# GMR.net
KiCad netlist of a schematic drawn in Altium Designer
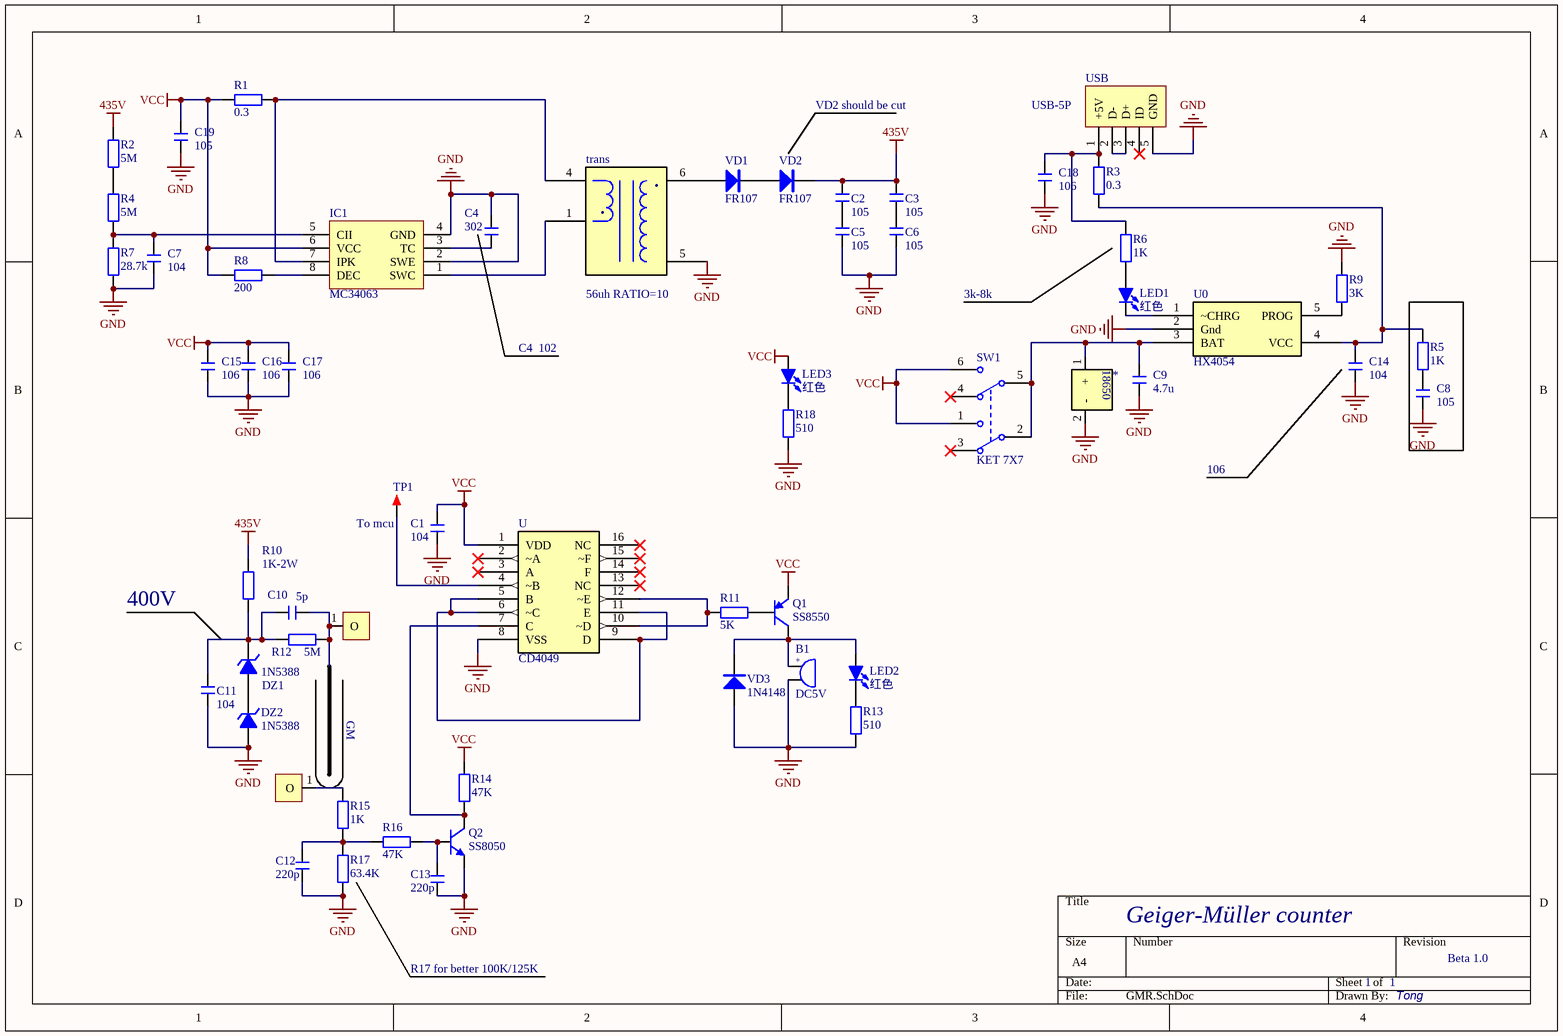
[diagram p0: GMR.SchDoc]

(export (version "E")
  (design (tool "Eeschema 10.0.6"))
  (components
    (comp (ref "*")
      (value "Component_1")
      (footprint "18650base")
      (libsource (lib "18650") (part "Component_1"))
    )
    (comp (ref "B1")
      (value "DC5V")
      (footprint "BEEP 7.6X12X7.5")
      (description "蜂鸣器")
      (fields (field (name "版权归属") "源创客"))
      (libsource (lib "未分类器件") (part "BEEP"))
    )
    (comp (ref "C1")
      (value "104")
      (footprint "C 0603")
      (description "瓷片电容-贴片")
      (libsource (lib "无源器件") (part "Cap-CER-SMD"))
    )
    (comp (ref "C2")
      (value "105")
      (footprint "C 1812")
      (description "瓷片电容-贴片")
      (libsource (lib "无源器件") (part "Cap-CER-SMD"))
    )
    (comp (ref "C3")
      (value "105")
      (footprint "C 1812")
      (description "瓷片电容-贴片")
      (libsource (lib "无源器件") (part "Cap-CER-SMD"))
    )
    (comp (ref "C4")
      (value "302")
      (footprint "C 0603")
      (description "瓷片电容-贴片")
      (libsource (lib "无源器件") (part "Cap-CER-SMD"))
    )
    (comp (ref "C5")
      (value "105")
      (footprint "C 1812")
      (description "瓷片电容-贴片")
      (libsource (lib "无源器件") (part "Cap-CER-SMD"))
    )
    (comp (ref "C6")
      (value "105")
      (footprint "C 1812")
      (description "瓷片电容-贴片")
      (libsource (lib "无源器件") (part "Cap-CER-SMD"))
    )
    (comp (ref "C7")
      (value "104")
      (footprint "C 0603")
      (description "瓷片电容-贴片")
      (libsource (lib "无源器件") (part "Cap-CER-SMD"))
    )
    (comp (ref "C8")
      (value "105")
      (footprint "C 0603")
      (description "瓷片电容-贴片")
      (libsource (lib "无源器件") (part "Cap-CER-SMD"))
    )
    (comp (ref "C9")
      (value "4.7u")
      (footprint "C 0603")
      (description "瓷片电容-贴片")
      (libsource (lib "无源器件") (part "Cap-CER-SMD"))
    )
    (comp (ref "C10")
      (value "5p")
      (footprint "C 1206")
      (description "瓷片电容-贴片")
      (libsource (lib "无源器件") (part "Cap-CER-SMD"))
    )
    (comp (ref "C11")
      (value "104")
      (footprint "C 1812")
      (description "瓷片电容-贴片")
      (libsource (lib "无源器件") (part "Cap-CER-SMD"))
    )
    (comp (ref "C12")
      (value "220p")
      (footprint "C 0603")
      (description "瓷片电容-贴片")
      (libsource (lib "无源器件") (part "Cap-CER-SMD"))
    )
    (comp (ref "C13")
      (value "220p")
      (footprint "C 0603")
      (description "瓷片电容-贴片")
      (libsource (lib "无源器件") (part "Cap-CER-SMD"))
    )
    (comp (ref "C14")
      (value "104")
      (footprint "C 0603")
      (description "瓷片电容-贴片")
      (libsource (lib "无源器件") (part "Cap-CER-SMD"))
    )
    (comp (ref "C15")
      (value "106")
      (footprint "C 0603")
      (description "瓷片电容-贴片")
      (libsource (lib "无源器件") (part "Cap-CER-SMD"))
    )
    (comp (ref "C16")
      (value "106")
      (footprint "C 0603")
      (description "瓷片电容-贴片")
      (libsource (lib "无源器件") (part "Cap-CER-SMD"))
    )
    (comp (ref "C17")
      (value "106")
      (footprint "C 0603")
      (description "瓷片电容-贴片")
      (libsource (lib "无源器件") (part "Cap-CER-SMD"))
    )
    (comp (ref "C18")
      (value "106")
      (footprint "C 0603")
      (description "瓷片电容-贴片")
      (libsource (lib "无源器件") (part "Cap-CER-SMD"))
    )
    (comp (ref "C19")
      (value "105")
      (footprint "C 0603")
      (description "瓷片电容-贴片")
      (libsource (lib "无源器件") (part "Cap-CER-SMD"))
    )
    (comp (ref "DZ1")
      (value "1N5388")
      (footprint "wydiode")
      (description "30V/0.5W稳压管")
      (fields (field (name "版权归属") "源创客"))
      (libsource (lib "二极管-整流桥") (part "1N5256"))
    )
    (comp (ref "DZ2")
      (value "1N5388")
      (footprint "wydiode")
      (description "30V/0.5W稳压管")
      (fields (field (name "版权归属") "源创客"))
      (libsource (lib "二极管-整流桥") (part "1N5256"))
    )
    (comp (ref "IC1")
      (value "MC34063")
      (footprint "SOP8_L")
      (description "DC升降压芯片")
      (fields (field (name "版权归属") "源创客"))
      (libsource (lib "IC芯片") (part "MC34063"))
    )
    (comp (ref "LED1")
      (value "红色")
      (footprint "LED 0603B")
      (description "贴片LED")
      (libsource (lib "声光-传感器") (part "LED-SMD"))
    )
    (comp (ref "LED2")
      (value "红色")
      (footprint "LED")
      (description "贴片LED")
      (libsource (lib "声光-传感器") (part "LED-SMD"))
    )
    (comp (ref "LED3")
      (value "红色")
      (footprint "LED")
      (description "贴片LED")
      (libsource (lib "声光-传感器") (part "LED-SMD"))
    )
    (comp (ref "Q1")
      (value "SS8550")
      (footprint "SOT23-3N")
      (description "高频放大-PNP型")
      (fields (field (name "版权归属") "源创客"))
      (libsource (lib "三极管") (part "8550-SMD"))
    )
    (comp (ref "Q2")
      (value "SS8050")
      (footprint "SOT23-3L")
      (description "高频放大-NPN型")
      (fields (field (name "版权归属") "源创客"))
      (libsource (lib "三极管") (part "8050-SMD"))
    )
    (comp (ref "R1")
      (value "0.3")
      (footprint "Res-SMD-1206")
      (description "固定电阻器-贴片")
      (libsource (lib "无源器件") (part "Res-Fixed-SMD"))
    )
    (comp (ref "R2")
      (value "5M")
      (footprint "Res-SMD-1206")
      (description "固定电阻器-贴片")
      (libsource (lib "无源器件") (part "Res-Fixed-SMD"))
    )
    (comp (ref "R3")
      (value "0.3")
      (footprint "Res-SMD-1206")
      (description "固定电阻器-贴片")
      (libsource (lib "无源器件") (part "Res-Fixed-SMD"))
    )
    (comp (ref "R4")
      (value "5M")
      (footprint "Res-SMD-1206")
      (description "固定电阻器-贴片")
      (libsource (lib "无源器件") (part "Res-Fixed-SMD"))
    )
    (comp (ref "R5")
      (value "1K")
      (footprint "Res-SMD-0603")
      (description "固定电阻器-贴片")
      (libsource (lib "无源器件") (part "Res-Fixed-SMD"))
    )
    (comp (ref "R6")
      (value "1K")
      (footprint "Res-SMD-0603")
      (description "固定电阻器-贴片")
      (libsource (lib "无源器件") (part "Res-Fixed-SMD"))
    )
    (comp (ref "R7")
      (value "28.7k")
      (footprint "Res-SMD-0603")
      (description "固定电阻器-贴片")
      (libsource (lib "无源器件") (part "Res-Fixed-SMD"))
    )
    (comp (ref "R8")
      (value "200")
      (footprint "Res-SMD-0603")
      (description "固定电阻器-贴片")
      (libsource (lib "无源器件") (part "Res-Fixed-SMD"))
    )
    (comp (ref "R9")
      (value "3K")
      (footprint "Res-SMD-0603")
      (description "固定电阻器-贴片")
      (libsource (lib "无源器件") (part "Res-Fixed-SMD"))
    )
    (comp (ref "R10")
      (value "1K-2W")
      (footprint "Res-Axial-2W")
      (description "固定电阻器-直插")
      (libsource (lib "无源器件") (part "Res-Fixed-Axial"))
    )
    (comp (ref "R11")
      (value "5K")
      (footprint "Res-SMD-0603")
      (description "固定电阻器-贴片")
      (libsource (lib "无源器件") (part "Res-Fixed-SMD"))
    )
    (comp (ref "R12")
      (value "5M")
      (footprint "Res-Axial-1/4W")
      (description "固定电阻器-直插")
      (libsource (lib "无源器件") (part "Res-Fixed-Axial"))
    )
    (comp (ref "R13")
      (value "510")
      (footprint "Res-SMD-0603")
      (description "固定电阻器-贴片")
      (libsource (lib "无源器件") (part "Res-Fixed-SMD"))
    )
    (comp (ref "R14")
      (value "47K")
      (footprint "Res-SMD-0603")
      (description "固定电阻器-贴片")
      (libsource (lib "无源器件") (part "Res-Fixed-SMD"))
    )
    (comp (ref "R15")
      (value "1K")
      (footprint "Res-SMD-0603")
      (description "固定电阻器-贴片")
      (libsource (lib "无源器件") (part "Res-Fixed-SMD"))
    )
    (comp (ref "R16")
      (value "47K")
      (footprint "Res-SMD-0603")
      (description "固定电阻器-贴片")
      (libsource (lib "无源器件") (part "Res-Fixed-SMD"))
    )
    (comp (ref "R17")
      (value "63.4K")
      (footprint "Res-SMD-0603")
      (description "固定电阻器-贴片")
      (libsource (lib "无源器件") (part "Res-Fixed-SMD"))
    )
    (comp (ref "R18")
      (value "510")
      (footprint "Res-SMD-0603")
      (description "固定电阻器-贴片")
      (libsource (lib "无源器件") (part "Res-Fixed-SMD"))
    )
    (comp (ref "SW1")
      (value "KET 7X7")
      (footprint "5.8*5.8")
      (description "7*7自锁开关")
      (fields (field (name "版权归属") "源创客"))
      (libsource (lib "按键-开关-继电器") (part "KET 7X7"))
    )
    (comp (ref "TP1")
      (value "To mcu")
      (footprint "TEST TP1.4_B")
      (description "测试环")
      (fields (field (name "版权归属") "源创客"))
      (libsource (lib "未分类器件") (part "TEST TP"))
    )
    (comp (ref "trans") (value "~") (footprint "trans") (libsource (lib "trans1") (part "Component_1")))
    (comp (ref "tube1")
      (value "tube1")
      (footprint "PCBComponent_1")
      (libsource (lib "") (part "Component_1_1"))
    )
    (comp (ref "tube2")
      (value "tube2")
      (footprint "PCBComponent_1")
      (libsource (lib "tubebase") (part "Component_1"))
    )
    (comp (ref "U") (value "CD4049") (footprint "SOP16_L") (libsource (lib "CD4049") (part "Component_1")))
    (comp (ref "U0") (value "HX4054") (footprint "SOT23-5L") (libsource (lib "HX4054A") (part "Component_1")))
    (comp (ref "USB")
      (value "USB-5P")
      (footprint "USB-MICRO_B")
      (description "微型USB母座")
      (fields (field (name "版权归属") "源创客"))
      (libsource (lib "接口类") (part "USB-5P"))
    )
    (comp (ref "VD1")
      (value "FR107")
      (footprint "SOD-123F")
      (description "快恢复整流二极管")
      (fields (field (name "版权归属") "源创客"))
      (libsource (lib "二极管-整流桥") (part "FR107"))
    )
    (comp (ref "VD2")
      (value "FR107")
      (footprint "SOD-123F")
      (description "快恢复整流二极管")
      (fields (field (name "版权归属") "源创客"))
      (libsource (lib "二极管-整流桥") (part "FR107"))
    )
    (comp (ref "VD3")
      (value "1N4148")
      (footprint "SOD-123F")
      (description "高速开关二极管")
      (fields (field (name "版权归属") "源创客"))
      (libsource (lib "二极管-整流桥") (part "1N4148"))
    )
  )
  (nets
    (net (code "1") (name "435V") (class "Default")
      (node (ref "C2") (pin "1") (pinfunction "1_1") (pintype "passive"))
      (node (ref "C3") (pin "1") (pinfunction "1_1") (pintype "passive"))
      (node (ref "R10") (pin "2") (pinfunction "2_2") (pintype "passive"))
      (node (ref "R2") (pin "2") (pinfunction "2_2") (pintype "passive"))
      (node (ref "VD2") (pin "2") (pinfunction "K_2") (pintype "passive"))
    )
    (net (code "2") (name "GND") (class "Default")
      (node (ref "*") (pin "2") (pinfunction "-_2") (pintype "passive"))
      (node (ref "B1") (pin "2") (pinfunction "2_2") (pintype "passive"))
      (node (ref "C1") (pin "2") (pinfunction "2_2") (pintype "passive"))
      (node (ref "C11") (pin "2") (pinfunction "2_2") (pintype "passive"))
      (node (ref "C12") (pin "2") (pinfunction "2_2") (pintype "passive"))
      (node (ref "C13") (pin "2") (pinfunction "2_2") (pintype "passive"))
      (node (ref "C14") (pin "2") (pinfunction "2_2") (pintype "passive"))
      (node (ref "C15") (pin "2") (pinfunction "2_2") (pintype "passive"))
      (node (ref "C16") (pin "2") (pinfunction "2_2") (pintype "passive"))
      (node (ref "C17") (pin "2") (pinfunction "2_2") (pintype "passive"))
      (node (ref "C18") (pin "2") (pinfunction "2_2") (pintype "passive"))
      (node (ref "C19") (pin "2") (pinfunction "2_2") (pintype "passive"))
      (node (ref "C4") (pin "1") (pinfunction "1_1") (pintype "passive"))
      (node (ref "C5") (pin "2") (pinfunction "2_2") (pintype "passive"))
      (node (ref "C6") (pin "2") (pinfunction "2_2") (pintype "passive"))
      (node (ref "C7") (pin "2") (pinfunction "2_2") (pintype "passive"))
      (node (ref "C8") (pin "2") (pinfunction "2_2") (pintype "passive"))
      (node (ref "C9") (pin "2") (pinfunction "2_2") (pintype "passive"))
      (node (ref "DZ2") (pin "1") (pinfunction "A_1") (pintype "passive"))
      (node (ref "IC1") (pin "2") (pinfunction "SWE_2") (pintype "passive"))
      (node (ref "IC1") (pin "4") (pinfunction "GND_4") (pintype "passive"))
      (node (ref "Q2") (pin "2") (pinfunction "E_2") (pintype "passive"))
      (node (ref "R13") (pin "1") (pinfunction "1_1") (pintype "passive"))
      (node (ref "R17") (pin "1") (pinfunction "1_1") (pintype "passive"))
      (node (ref "R18") (pin "1") (pinfunction "1_1") (pintype "passive"))
      (node (ref "R7") (pin "1") (pinfunction "1_1") (pintype "passive"))
      (node (ref "R9") (pin "1") (pinfunction "1_1") (pintype "passive"))
      (node (ref "U") (pin "8") (pinfunction "VSS_8") (pintype "passive"))
      (node (ref "U0") (pin "2") (pinfunction "Gnd_2") (pintype "passive"))
      (node (ref "USB") (pin "5") (pinfunction "GND_5") (pintype "passive"))
      (node (ref "VD3") (pin "1") (pinfunction "A_1") (pintype "passive"))
      (node (ref "trans") (pin "5") (pinfunction "5_5") (pintype "passive"))
    )
    (net (code "3") (name "Net-(*-+)") (class "Default")
      (node (ref "*") (pin "1") (pinfunction "+_1") (pintype "passive"))
      (node (ref "C9") (pin "1") (pinfunction "1_1") (pintype "passive"))
      (node (ref "SW1") (pin "2") (pinfunction "COM2_2") (pintype "passive"))
      (node (ref "SW1") (pin "5") (pinfunction "COM2_5") (pintype "passive"))
      (node (ref "U0") (pin "3") (pinfunction "BAT_3") (pintype "passive"))
    )
    (net (code "4") (name "Net-(C2-Pad2)") (class "Default")
      (node (ref "C2") (pin "2") (pinfunction "2_2") (pintype "passive"))
      (node (ref "C5") (pin "1") (pinfunction "1_1") (pintype "passive"))
    )
    (net (code "5") (name "Net-(C3-Pad2)") (class "Default")
      (node (ref "C3") (pin "2") (pinfunction "2_2") (pintype "passive"))
      (node (ref "C6") (pin "1") (pinfunction "1_1") (pintype "passive"))
    )
    (net (code "6") (name "Net-(C12-Pad1)") (class "Default")
      (node (ref "C12") (pin "1") (pinfunction "1_1") (pintype "passive"))
      (node (ref "R15") (pin "1") (pinfunction "1_1") (pintype "passive"))
      (node (ref "R16") (pin "2") (pinfunction "2_2") (pintype "passive"))
      (node (ref "R17") (pin "2") (pinfunction "2_2") (pintype "passive"))
    )
    (net (code "7") (name "Net-(DZ1-A)") (class "Default")
      (node (ref "DZ1") (pin "1") (pinfunction "A_1") (pintype "passive"))
      (node (ref "DZ2") (pin "2") (pinfunction "K_2") (pintype "passive"))
    )
    (net (code "8") (name "Net-(DZ1-K)") (class "Default")
      (node (ref "C10") (pin "2") (pinfunction "2_2") (pintype "passive"))
      (node (ref "C11") (pin "1") (pinfunction "1_1") (pintype "passive"))
      (node (ref "DZ1") (pin "2") (pinfunction "K_2") (pintype "passive"))
      (node (ref "R10") (pin "1") (pinfunction "1_1") (pintype "passive"))
      (node (ref "R12") (pin "1") (pinfunction "1_1") (pintype "passive"))
    )
    (net (code "9") (name "Net-(IC1-CII)") (class "Default")
      (node (ref "C7") (pin "1") (pinfunction "1_1") (pintype "passive"))
      (node (ref "IC1") (pin "5") (pinfunction "CII_5") (pintype "passive"))
      (node (ref "R4") (pin "1") (pinfunction "1_1") (pintype "passive"))
      (node (ref "R7") (pin "2") (pinfunction "2_2") (pintype "passive"))
    )
    (net (code "10") (name "Net-(IC1-DEC)") (class "Default")
      (node (ref "IC1") (pin "8") (pinfunction "DEC_8") (pintype "passive"))
      (node (ref "R8") (pin "1") (pinfunction "1_1") (pintype "passive"))
    )
    (net (code "11") (name "Net-(IC1-IPK)") (class "Default")
      (node (ref "IC1") (pin "7") (pinfunction "IPK_7") (pintype "passive"))
      (node (ref "R1") (pin "1") (pinfunction "1_1") (pintype "passive"))
      (node (ref "trans") (pin "4") (pinfunction "4_4") (pintype "passive"))
    )
    (net (code "12") (name "Net-(IC1-SWC)") (class "Default")
      (node (ref "IC1") (pin "1") (pinfunction "SWC_1") (pintype "passive"))
      (node (ref "trans") (pin "1") (pinfunction "1_1") (pintype "passive"))
    )
    (net (code "13") (name "Net-(IC1-TC)") (class "Default")
      (node (ref "C4") (pin "2") (pinfunction "2_2") (pintype "passive"))
      (node (ref "IC1") (pin "3") (pinfunction "TC_3") (pintype "passive"))
    )
    (net (code "14") (name "Net-(LED1-A)") (class "Default")
      (node (ref "LED1") (pin "1") (pinfunction "A_1") (pintype "passive"))
      (node (ref "R6") (pin "2") (pinfunction "2_2") (pintype "passive"))
    )
    (net (code "15") (name "Net-(LED1-K)") (class "Default")
      (node (ref "LED1") (pin "2") (pinfunction "K_2") (pintype "passive"))
      (node (ref "U0") (pin "1") (pinfunction "~CHRG_1") (pintype "passive"))
    )
    (net (code "16") (name "Net-(LED2-A)") (class "Default")
      (node (ref "B1") (pin "1") (pinfunction "1_1") (pintype "passive"))
      (node (ref "LED2") (pin "1") (pinfunction "A_1") (pintype "passive"))
      (node (ref "Q1") (pin "3") (pinfunction "C_3") (pintype "passive"))
      (node (ref "VD3") (pin "2") (pinfunction "K_2") (pintype "passive"))
    )
    (net (code "17") (name "Net-(LED2-K)") (class "Default")
      (node (ref "LED2") (pin "2") (pinfunction "K_2") (pintype "passive"))
      (node (ref "R13") (pin "2") (pinfunction "2_2") (pintype "passive"))
    )
    (net (code "18") (name "Net-(LED3-K)") (class "Default")
      (node (ref "LED3") (pin "2") (pinfunction "K_2") (pintype "passive"))
      (node (ref "R18") (pin "2") (pinfunction "2_2") (pintype "passive"))
    )
    (net (code "19") (name "Net-(Q1-B)") (class "Default")
      (node (ref "Q1") (pin "1") (pinfunction "B_1") (pintype "passive"))
      (node (ref "R11") (pin "2") (pinfunction "2_2") (pintype "passive"))
    )
    (net (code "20") (name "Net-(Q2-B)") (class "Default")
      (node (ref "C13") (pin "1") (pinfunction "1_1") (pintype "passive"))
      (node (ref "Q2") (pin "1") (pinfunction "B_1") (pintype "passive"))
      (node (ref "R16") (pin "1") (pinfunction "1_1") (pintype "passive"))
    )
    (net (code "21") (name "Net-(Q2-C)") (class "Default")
      (node (ref "Q2") (pin "3") (pinfunction "C_3") (pintype "passive"))
      (node (ref "R14") (pin "2") (pinfunction "2_2") (pintype "passive"))
      (node (ref "U") (pin "7") (pinfunction "C_7") (pintype "passive"))
    )
    (net (code "22") (name "Net-(R2-Pad1)") (class "Default")
      (node (ref "R2") (pin "1") (pinfunction "1_1") (pintype "passive"))
      (node (ref "R4") (pin "2") (pinfunction "2_2") (pintype "passive"))
    )
    (net (code "23") (name "Net-(U-B)") (class "Default")
      (node (ref "U") (pin "11") (pinfunction "E_11") (pintype "passive"))
      (node (ref "U") (pin "5") (pinfunction "B_5") (pintype "passive"))
      (node (ref "U") (pin "6") (pinfunction "~C_6") (pintype "output"))
      (node (ref "U") (pin "9") (pinfunction "D_9") (pintype "passive"))
    )
    (net (code "24") (name "Net-(U-~B)") (class "Default")
      (node (ref "TP1") (pin "1") (pinfunction "1_1") (pintype "passive"))
      (node (ref "U") (pin "4") (pinfunction "~B_4") (pintype "output"))
    )
    (net (code "25") (name "Net-(U-~D)") (class "Default")
      (node (ref "R11") (pin "1") (pinfunction "1_1") (pintype "passive"))
      (node (ref "U") (pin "10") (pinfunction "~D_10") (pintype "output"))
      (node (ref "U") (pin "12") (pinfunction "~E_12") (pintype "output"))
    )
    (net (code "26") (name "Net-(U0-PROG)") (class "Default")
      (node (ref "R9") (pin "2") (pinfunction "2_2") (pintype "passive"))
      (node (ref "U0") (pin "5") (pinfunction "PROG_5") (pintype "passive"))
    )
    (net (code "27") (name "Net-(U0-VCC)") (class "Default")
      (node (ref "C14") (pin "1") (pinfunction "1_1") (pintype "passive"))
      (node (ref "R3") (pin "2") (pinfunction "2_2") (pintype "passive"))
      (node (ref "R5") (pin "1") (pinfunction "1_1") (pintype "passive"))
      (node (ref "U0") (pin "4") (pinfunction "VCC_4") (pintype "passive"))
    )
    (net (code "28") (name "Net-(USB-+5V)") (class "Default")
      (node (ref "C18") (pin "1") (pinfunction "1_1") (pintype "passive"))
      (node (ref "R3") (pin "1") (pinfunction "1_1") (pintype "passive"))
      (node (ref "R6") (pin "1") (pinfunction "1_1") (pintype "passive"))
      (node (ref "USB") (pin "1") (pinfunction "+5V_1") (pintype "passive"))
    )
    (net (code "29") (name "Net-(USB-D+)") (class "Default")
      (node (ref "USB") (pin "2") (pinfunction "D-_2") (pintype "passive"))
      (node (ref "USB") (pin "3") (pinfunction "D+_3") (pintype "passive"))
    )
    (net (code "30") (name "Net-(VD1-A)") (class "Default")
      (node (ref "VD1") (pin "1") (pinfunction "A_1") (pintype "passive"))
      (node (ref "trans") (pin "6") (pinfunction "6_6") (pintype "passive"))
    )
    (net (code "31") (name "Net-(VD1-K)") (class "Default")
      (node (ref "VD1") (pin "2") (pinfunction "K_2") (pintype "passive"))
      (node (ref "VD2") (pin "1") (pinfunction "A_1") (pintype "passive"))
    )
    (net (code "32") (name "Net-(tube1-O)") (class "Default")
      (node (ref "R15") (pin "2") (pinfunction "2_2") (pintype "passive"))
      (node (ref "tube1") (pin "1") (pinfunction "O_1") (pintype "passive"))
    )
    (net (code "33") (name "Net-(tube2-O)") (class "Default")
      (node (ref "C10") (pin "1") (pinfunction "1_1") (pintype "passive"))
      (node (ref "R12") (pin "2") (pinfunction "2_2") (pintype "passive"))
      (node (ref "tube2") (pin "1") (pinfunction "O_1") (pintype "passive"))
    )
    (net (code "34") (name "VCC") (class "Default")
      (node (ref "C1") (pin "1") (pinfunction "1_1") (pintype "passive"))
      (node (ref "C15") (pin "1") (pinfunction "1_1") (pintype "passive"))
      (node (ref "C16") (pin "1") (pinfunction "1_1") (pintype "passive"))
      (node (ref "C17") (pin "1") (pinfunction "1_1") (pintype "passive"))
      (node (ref "C19") (pin "1") (pinfunction "1_1") (pintype "passive"))
      (node (ref "IC1") (pin "6") (pinfunction "VCC_6") (pintype "passive"))
      (node (ref "LED3") (pin "1") (pinfunction "A_1") (pintype "passive"))
      (node (ref "Q1") (pin "2") (pinfunction "E_2") (pintype "passive"))
      (node (ref "R1") (pin "2") (pinfunction "2_2") (pintype "passive"))
      (node (ref "R14") (pin "1") (pinfunction "1_1") (pintype "passive"))
      (node (ref "R8") (pin "2") (pinfunction "2_2") (pintype "passive"))
      (node (ref "SW1") (pin "1") (pinfunction "NC1_1") (pintype "passive"))
      (node (ref "SW1") (pin "6") (pinfunction "NC2_6") (pintype "passive"))
      (node (ref "U") (pin "1") (pinfunction "VDD_1") (pintype "passive"))
    )
    (net (code "35") (name "unconnected-(C8-Pad1)") (class "Default")
      (node (ref "C8") (pin "1") (pinfunction "1_1") (pintype "passive"))
    )
    (net (code "36") (name "unconnected-(R5-Pad2)") (class "Default")
      (node (ref "R5") (pin "2") (pinfunction "2_2") (pintype "passive"))
    )
    (net (code "37") (name "unconnected-(SW1-NO1-Pad3)") (class "Default")
      (node (ref "SW1") (pin "3") (pinfunction "NO1_3") (pintype "passive+no_connect"))
    )
    (net (code "38") (name "unconnected-(SW1-NO2-Pad4)") (class "Default")
      (node (ref "SW1") (pin "4") (pinfunction "NO2_4") (pintype "passive+no_connect"))
    )
    (net (code "39") (name "unconnected-(U-A-Pad3)") (class "Default")
      (node (ref "U") (pin "3") (pinfunction "A_3") (pintype "passive+no_connect"))
    )
    (net (code "40") (name "unconnected-(U-F-Pad14)") (class "Default")
      (node (ref "U") (pin "14") (pinfunction "F_14") (pintype "passive+no_connect"))
    )
    (net (code "41") (name "unconnected-(U-NC-Pad13)") (class "Default")
      (node (ref "U") (pin "13") (pinfunction "NC_13") (pintype "passive+no_connect"))
    )
    (net (code "42") (name "unconnected-(U-NC-Pad16)") (class "Default")
      (node (ref "U") (pin "16") (pinfunction "NC_16") (pintype "passive+no_connect"))
    )
    (net (code "43") (name "unconnected-(U-~A-Pad2)") (class "Default")
      (node (ref "U") (pin "2") (pinfunction "~A_2") (pintype "output+no_connect"))
    )
    (net (code "44") (name "unconnected-(U-~F-Pad15)") (class "Default")
      (node (ref "U") (pin "15") (pinfunction "~F_15") (pintype "output+no_connect"))
    )
    (net (code "45") (name "unconnected-(USB-ID-Pad4)") (class "Default")
      (node (ref "USB") (pin "4") (pinfunction "ID_4") (pintype "passive+no_connect"))
    )
  )
)
